# untitled.net
KiCad netlist of a schematic drawn in EAGLE
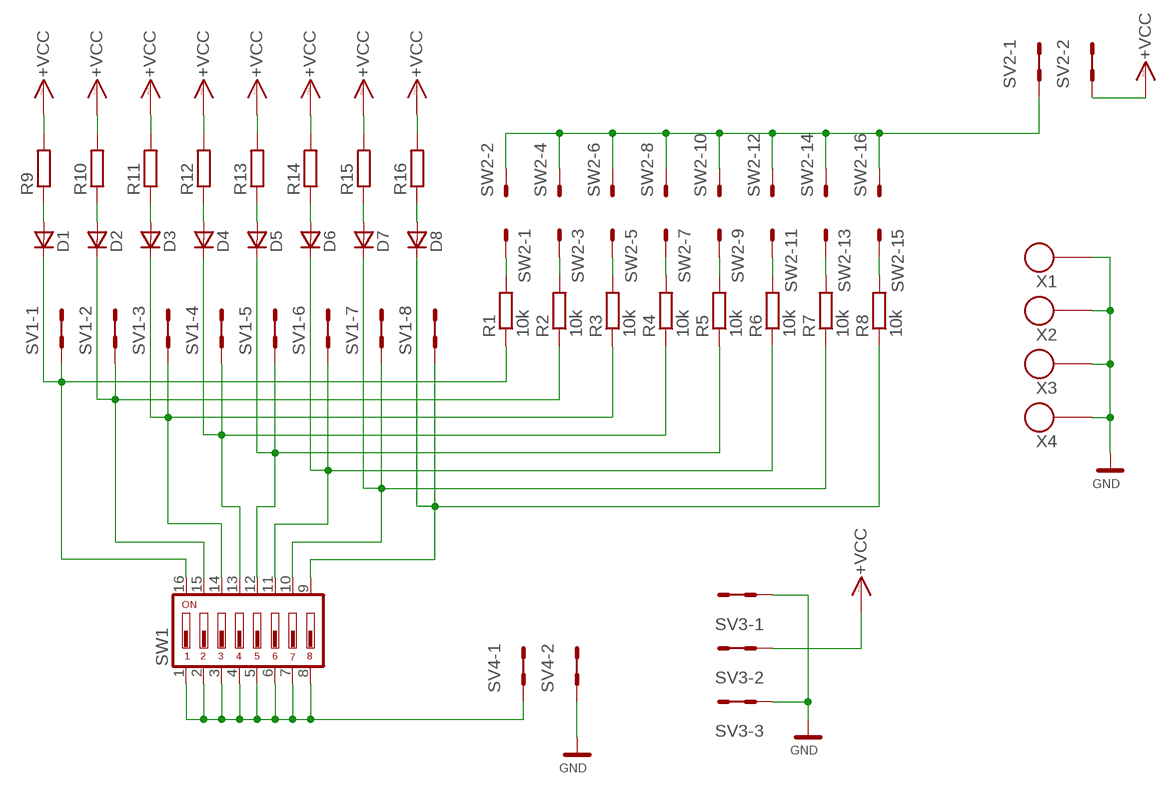
[diagram p0: schematic, sheet 1]

(export (version "E")
  (design (tool "Eeschema 10.0.6"))
  (components
    (comp (ref "D1")
      (value "LED1206_2")
      (footprint "eagle-import:1206_2")
      (libsource (lib "eagle-import") (part "LED1206_2"))
    )
    (comp (ref "D2")
      (value "LED1206_2")
      (footprint "eagle-import:1206_2")
      (libsource (lib "eagle-import") (part "LED1206_2"))
    )
    (comp (ref "D3")
      (value "LED1206_2")
      (footprint "eagle-import:1206_2")
      (libsource (lib "eagle-import") (part "LED1206_2"))
    )
    (comp (ref "D4")
      (value "LED1206_2")
      (footprint "eagle-import:1206_2")
      (libsource (lib "eagle-import") (part "LED1206_2"))
    )
    (comp (ref "D5")
      (value "LED1206_2")
      (footprint "eagle-import:1206_2")
      (libsource (lib "eagle-import") (part "LED1206_2"))
    )
    (comp (ref "D6")
      (value "LED1206_2")
      (footprint "eagle-import:1206_2")
      (libsource (lib "eagle-import") (part "LED1206_2"))
    )
    (comp (ref "D7")
      (value "LED1206_2")
      (footprint "eagle-import:1206_2")
      (libsource (lib "eagle-import") (part "LED1206_2"))
    )
    (comp (ref "D8")
      (value "LED1206_2")
      (footprint "eagle-import:1206_2")
      (libsource (lib "eagle-import") (part "LED1206_2"))
    )
    (comp (ref "R1")
      (value "10k")
      (footprint "eagle-import:0805")
      (libsource (lib "eagle-import") (part "R0805"))
    )
    (comp (ref "R2")
      (value "10k")
      (footprint "eagle-import:0805")
      (libsource (lib "eagle-import") (part "R0805"))
    )
    (comp (ref "R3")
      (value "10k")
      (footprint "eagle-import:0805")
      (libsource (lib "eagle-import") (part "R0805"))
    )
    (comp (ref "R4")
      (value "10k")
      (footprint "eagle-import:0805")
      (libsource (lib "eagle-import") (part "R0805"))
    )
    (comp (ref "R5")
      (value "10k")
      (footprint "eagle-import:0805")
      (libsource (lib "eagle-import") (part "R0805"))
    )
    (comp (ref "R6")
      (value "10k")
      (footprint "eagle-import:0805")
      (libsource (lib "eagle-import") (part "R0805"))
    )
    (comp (ref "R7")
      (value "10k")
      (footprint "eagle-import:0805")
      (libsource (lib "eagle-import") (part "R0805"))
    )
    (comp (ref "R8")
      (value "10k")
      (footprint "eagle-import:0805")
      (libsource (lib "eagle-import") (part "R0805"))
    )
    (comp (ref "R9")
      (value "R0805")
      (footprint "eagle-import:0805")
      (libsource (lib "eagle-import") (part "R0805"))
    )
    (comp (ref "R10")
      (value "R0805")
      (footprint "eagle-import:0805")
      (libsource (lib "eagle-import") (part "R0805"))
    )
    (comp (ref "R11")
      (value "R0805")
      (footprint "eagle-import:0805")
      (libsource (lib "eagle-import") (part "R0805"))
    )
    (comp (ref "R12")
      (value "R0805")
      (footprint "eagle-import:0805")
      (libsource (lib "eagle-import") (part "R0805"))
    )
    (comp (ref "R13")
      (value "R0805")
      (footprint "eagle-import:0805")
      (libsource (lib "eagle-import") (part "R0805"))
    )
    (comp (ref "R14")
      (value "R0805")
      (footprint "eagle-import:0805")
      (libsource (lib "eagle-import") (part "R0805"))
    )
    (comp (ref "R15")
      (value "R0805")
      (footprint "eagle-import:0805")
      (libsource (lib "eagle-import") (part "R0805"))
    )
    (comp (ref "R16")
      (value "R0805")
      (footprint "eagle-import:0805")
      (libsource (lib "eagle-import") (part "R0805"))
    )
    (comp (ref "SV1")
      (value "MA08-2")
      (footprint "eagle-import:MA08-2")
      (libsource (lib "eagle-import") (part "MA08-2"))
    )
    (comp (ref "SV2")
      (value "MA02-2")
      (footprint "eagle-import:MA02-2")
      (libsource (lib "eagle-import") (part "MA02-2"))
    )
    (comp (ref "SV3")
      (value "MA03-2")
      (footprint "eagle-import:MA03-2")
      (libsource (lib "eagle-import") (part "MA03-2"))
    )
    (comp (ref "SV4")
      (value "MA02-2")
      (footprint "eagle-import:MA02-2")
      (libsource (lib "eagle-import") (part "MA02-2"))
    )
    (comp (ref "SW1")
      (value "DIP-08")
      (footprint "eagle-import:DIP08SW")
      (libsource (lib "eagle-import") (part "DIP-08"))
    )
    (comp (ref "SW2")
      (value "MA08-3")
      (footprint "eagle-import:MA08-2")
      (libsource (lib "eagle-import") (part "MA08-3"))
    )
    (comp (ref "X1")
      (value "SROUB3M")
      (footprint "eagle-import:SROUB3M")
      (libsource (lib "eagle-import") (part "SROUB3M"))
    )
    (comp (ref "X2")
      (value "SROUB3M")
      (footprint "eagle-import:SROUB3M")
      (libsource (lib "eagle-import") (part "SROUB3M"))
    )
    (comp (ref "X3")
      (value "SROUB3M")
      (footprint "eagle-import:SROUB3M")
      (libsource (lib "eagle-import") (part "SROUB3M"))
    )
    (comp (ref "X4")
      (value "SROUB3M")
      (footprint "eagle-import:SROUB3M")
      (libsource (lib "eagle-import") (part "SROUB3M"))
    )
  )
  (nets
    (net (code "1") (name "+VCC") (class "Default")
      (node (ref "R10") (pin "2") (pinfunction "2_2") (pintype "passive"))
      (node (ref "R11") (pin "2") (pinfunction "2_2") (pintype "passive"))
      (node (ref "R12") (pin "2") (pinfunction "2_2") (pintype "passive"))
      (node (ref "R13") (pin "2") (pinfunction "2_2") (pintype "passive"))
      (node (ref "R14") (pin "2") (pinfunction "2_2") (pintype "passive"))
      (node (ref "R15") (pin "2") (pinfunction "2_2") (pintype "passive"))
      (node (ref "R16") (pin "2") (pinfunction "2_2") (pintype "passive"))
      (node (ref "R9") (pin "2") (pinfunction "2_2") (pintype "passive"))
      (node (ref "SV2") (pin "3") (pinfunction "K_3") (pintype "passive"))
      (node (ref "SV2") (pin "4") (pinfunction "K_4") (pintype "passive"))
      (node (ref "SV3") (pin "3") (pinfunction "K_3") (pintype "passive"))
      (node (ref "SV3") (pin "4") (pinfunction "K_4") (pintype "passive"))
    )
    (net (code "2") (name "GND") (class "Default")
      (node (ref "SV3") (pin "1") (pinfunction "K_1") (pintype "passive"))
      (node (ref "SV3") (pin "2") (pinfunction "K_2") (pintype "passive"))
      (node (ref "SV3") (pin "5") (pinfunction "K_5") (pintype "passive"))
      (node (ref "SV3") (pin "6") (pinfunction "K_6") (pintype "passive"))
      (node (ref "SV4") (pin "3") (pinfunction "K_3") (pintype "passive"))
      (node (ref "SV4") (pin "4") (pinfunction "K_4") (pintype "passive"))
      (node (ref "X1") (pin "P$1") (pinfunction "P$1_P$1") (pintype "bidirectional"))
      (node (ref "X2") (pin "P$1") (pinfunction "P$1_P$1") (pintype "bidirectional"))
      (node (ref "X3") (pin "P$1") (pinfunction "P$1_P$1") (pintype "bidirectional"))
      (node (ref "X4") (pin "P$1") (pinfunction "P$1_P$1") (pintype "bidirectional"))
    )
    (net (code "3") (name "Net-(D1-PadA)") (class "Default")
      (node (ref "D1") (pin "A") (pinfunction "A_A") (pintype "passive"))
      (node (ref "R9") (pin "1") (pinfunction "1_1") (pintype "passive"))
    )
    (net (code "4") (name "Net-(D1-PadK)") (class "Default")
      (node (ref "D1") (pin "K") (pinfunction "K_K") (pintype "passive"))
      (node (ref "R1") (pin "1") (pinfunction "1_1") (pintype "passive"))
      (node (ref "SV1") (pin "1") (pinfunction "K_1") (pintype "passive"))
      (node (ref "SV1") (pin "2") (pinfunction "K_2") (pintype "passive"))
      (node (ref "SW1") (pin "16") (pinfunction "16_16") (pintype "passive"))
    )
    (net (code "5") (name "Net-(D2-PadA)") (class "Default")
      (node (ref "D2") (pin "A") (pinfunction "A_A") (pintype "passive"))
      (node (ref "R10") (pin "1") (pinfunction "1_1") (pintype "passive"))
    )
    (net (code "6") (name "Net-(D2-PadK)") (class "Default")
      (node (ref "D2") (pin "K") (pinfunction "K_K") (pintype "passive"))
      (node (ref "R2") (pin "1") (pinfunction "1_1") (pintype "passive"))
      (node (ref "SV1") (pin "3") (pinfunction "K_3") (pintype "passive"))
      (node (ref "SV1") (pin "4") (pinfunction "K_4") (pintype "passive"))
      (node (ref "SW1") (pin "15") (pinfunction "15_15") (pintype "passive"))
    )
    (net (code "7") (name "Net-(D3-PadA)") (class "Default")
      (node (ref "D3") (pin "A") (pinfunction "A_A") (pintype "passive"))
      (node (ref "R11") (pin "1") (pinfunction "1_1") (pintype "passive"))
    )
    (net (code "8") (name "Net-(D3-PadK)") (class "Default")
      (node (ref "D3") (pin "K") (pinfunction "K_K") (pintype "passive"))
      (node (ref "R3") (pin "1") (pinfunction "1_1") (pintype "passive"))
      (node (ref "SV1") (pin "5") (pinfunction "K_5") (pintype "passive"))
      (node (ref "SV1") (pin "6") (pinfunction "K_6") (pintype "passive"))
      (node (ref "SW1") (pin "14") (pinfunction "14_14") (pintype "passive"))
    )
    (net (code "9") (name "Net-(D4-PadA)") (class "Default")
      (node (ref "D4") (pin "A") (pinfunction "A_A") (pintype "passive"))
      (node (ref "R12") (pin "1") (pinfunction "1_1") (pintype "passive"))
    )
    (net (code "10") (name "Net-(D4-PadK)") (class "Default")
      (node (ref "D4") (pin "K") (pinfunction "K_K") (pintype "passive"))
      (node (ref "R4") (pin "1") (pinfunction "1_1") (pintype "passive"))
      (node (ref "SV1") (pin "7") (pinfunction "K_7") (pintype "passive"))
      (node (ref "SV1") (pin "8") (pinfunction "K_8") (pintype "passive"))
      (node (ref "SW1") (pin "13") (pinfunction "13_13") (pintype "passive"))
    )
    (net (code "11") (name "Net-(D5-PadA)") (class "Default")
      (node (ref "D5") (pin "A") (pinfunction "A_A") (pintype "passive"))
      (node (ref "R13") (pin "1") (pinfunction "1_1") (pintype "passive"))
    )
    (net (code "12") (name "Net-(D5-PadK)") (class "Default")
      (node (ref "D5") (pin "K") (pinfunction "K_K") (pintype "passive"))
      (node (ref "R5") (pin "1") (pinfunction "1_1") (pintype "passive"))
      (node (ref "SV1") (pin "10") (pinfunction "K_10") (pintype "passive"))
      (node (ref "SV1") (pin "9") (pinfunction "K_9") (pintype "passive"))
      (node (ref "SW1") (pin "12") (pinfunction "12_12") (pintype "passive"))
    )
    (net (code "13") (name "Net-(D6-PadA)") (class "Default")
      (node (ref "D6") (pin "A") (pinfunction "A_A") (pintype "passive"))
      (node (ref "R14") (pin "1") (pinfunction "1_1") (pintype "passive"))
    )
    (net (code "14") (name "Net-(D6-PadK)") (class "Default")
      (node (ref "D6") (pin "K") (pinfunction "K_K") (pintype "passive"))
      (node (ref "R6") (pin "1") (pinfunction "1_1") (pintype "passive"))
      (node (ref "SV1") (pin "11") (pinfunction "K_11") (pintype "passive"))
      (node (ref "SV1") (pin "12") (pinfunction "K_12") (pintype "passive"))
      (node (ref "SW1") (pin "11") (pinfunction "11_11") (pintype "passive"))
    )
    (net (code "15") (name "Net-(D7-PadA)") (class "Default")
      (node (ref "D7") (pin "A") (pinfunction "A_A") (pintype "passive"))
      (node (ref "R15") (pin "1") (pinfunction "1_1") (pintype "passive"))
    )
    (net (code "16") (name "Net-(D7-PadK)") (class "Default")
      (node (ref "D7") (pin "K") (pinfunction "K_K") (pintype "passive"))
      (node (ref "R7") (pin "1") (pinfunction "1_1") (pintype "passive"))
      (node (ref "SV1") (pin "13") (pinfunction "K_13") (pintype "passive"))
      (node (ref "SV1") (pin "14") (pinfunction "K_14") (pintype "passive"))
      (node (ref "SW1") (pin "10") (pinfunction "10_10") (pintype "passive"))
    )
    (net (code "17") (name "Net-(D8-PadA)") (class "Default")
      (node (ref "D8") (pin "A") (pinfunction "A_A") (pintype "passive"))
      (node (ref "R16") (pin "1") (pinfunction "1_1") (pintype "passive"))
    )
    (net (code "18") (name "Net-(D8-PadK)") (class "Default")
      (node (ref "D8") (pin "K") (pinfunction "K_K") (pintype "passive"))
      (node (ref "R8") (pin "1") (pinfunction "1_1") (pintype "passive"))
      (node (ref "SV1") (pin "15") (pinfunction "K_15") (pintype "passive"))
      (node (ref "SV1") (pin "16") (pinfunction "K_16") (pintype "passive"))
      (node (ref "SW1") (pin "9") (pinfunction "9_9") (pintype "passive"))
    )
    (net (code "19") (name "Net-(SV4A-K-Pad1)") (class "Default")
      (node (ref "SV4") (pin "1") (pinfunction "K_1") (pintype "passive"))
      (node (ref "SV4") (pin "2") (pinfunction "K_2") (pintype "passive"))
      (node (ref "SW1") (pin "1") (pinfunction "1_1") (pintype "passive"))
      (node (ref "SW1") (pin "2") (pinfunction "2_2") (pintype "passive"))
      (node (ref "SW1") (pin "3") (pinfunction "3_3") (pintype "passive"))
      (node (ref "SW1") (pin "4") (pinfunction "4_4") (pintype "passive"))
      (node (ref "SW1") (pin "5") (pinfunction "5_5") (pintype "passive"))
      (node (ref "SW1") (pin "6") (pinfunction "6_6") (pintype "passive"))
      (node (ref "SW1") (pin "7") (pinfunction "7_7") (pintype "passive"))
      (node (ref "SW1") (pin "8") (pinfunction "8_8") (pintype "passive"))
    )
    (net (code "20") (name "Net-(SW2A-P$1)") (class "Default")
      (node (ref "R1") (pin "2") (pinfunction "2_2") (pintype "passive"))
      (node (ref "SW2") (pin "1") (pinfunction "P$1_1") (pintype "passive"))
    )
    (net (code "21") (name "Net-(SW2B-P$1)") (class "Default")
      (node (ref "SV2") (pin "1") (pinfunction "K_1") (pintype "passive"))
      (node (ref "SV2") (pin "2") (pinfunction "K_2") (pintype "passive"))
      (node (ref "SW2") (pin "10") (pinfunction "P$1_10") (pintype "passive"))
      (node (ref "SW2") (pin "12") (pinfunction "P$1_12") (pintype "passive"))
      (node (ref "SW2") (pin "14") (pinfunction "P$1_14") (pintype "passive"))
      (node (ref "SW2") (pin "16") (pinfunction "P$1_16") (pintype "passive"))
      (node (ref "SW2") (pin "2") (pinfunction "P$1_2") (pintype "passive"))
      (node (ref "SW2") (pin "4") (pinfunction "P$1_4") (pintype "passive"))
      (node (ref "SW2") (pin "6") (pinfunction "P$1_6") (pintype "passive"))
      (node (ref "SW2") (pin "8") (pinfunction "P$1_8") (pintype "passive"))
    )
    (net (code "22") (name "Net-(SW2C-P$1)") (class "Default")
      (node (ref "R6") (pin "2") (pinfunction "2_2") (pintype "passive"))
      (node (ref "SW2") (pin "11") (pinfunction "P$1_11") (pintype "passive"))
    )
    (net (code "23") (name "Net-(SW2E-P$1)") (class "Default")
      (node (ref "R7") (pin "2") (pinfunction "2_2") (pintype "passive"))
      (node (ref "SW2") (pin "13") (pinfunction "P$1_13") (pintype "passive"))
    )
    (net (code "24") (name "Net-(SW2G-P$1)") (class "Default")
      (node (ref "R8") (pin "2") (pinfunction "2_2") (pintype "passive"))
      (node (ref "SW2") (pin "15") (pinfunction "P$1_15") (pintype "passive"))
    )
    (net (code "25") (name "Net-(SW2J-P$1)") (class "Default")
      (node (ref "R2") (pin "2") (pinfunction "2_2") (pintype "passive"))
      (node (ref "SW2") (pin "3") (pinfunction "P$1_3") (pintype "passive"))
    )
    (net (code "26") (name "Net-(SW2L-P$1)") (class "Default")
      (node (ref "R3") (pin "2") (pinfunction "2_2") (pintype "passive"))
      (node (ref "SW2") (pin "5") (pinfunction "P$1_5") (pintype "passive"))
    )
    (net (code "27") (name "Net-(SW2N-P$1)") (class "Default")
      (node (ref "R4") (pin "2") (pinfunction "2_2") (pintype "passive"))
      (node (ref "SW2") (pin "7") (pinfunction "P$1_7") (pintype "passive"))
    )
    (net (code "28") (name "Net-(SW2P-P$1)") (class "Default")
      (node (ref "R5") (pin "2") (pinfunction "2_2") (pintype "passive"))
      (node (ref "SW2") (pin "9") (pinfunction "P$1_9") (pintype "passive"))
    )
  )
)
